# Weather_Station_Data_v3.net
KiCad netlist of a schematic drawn in EAGLE
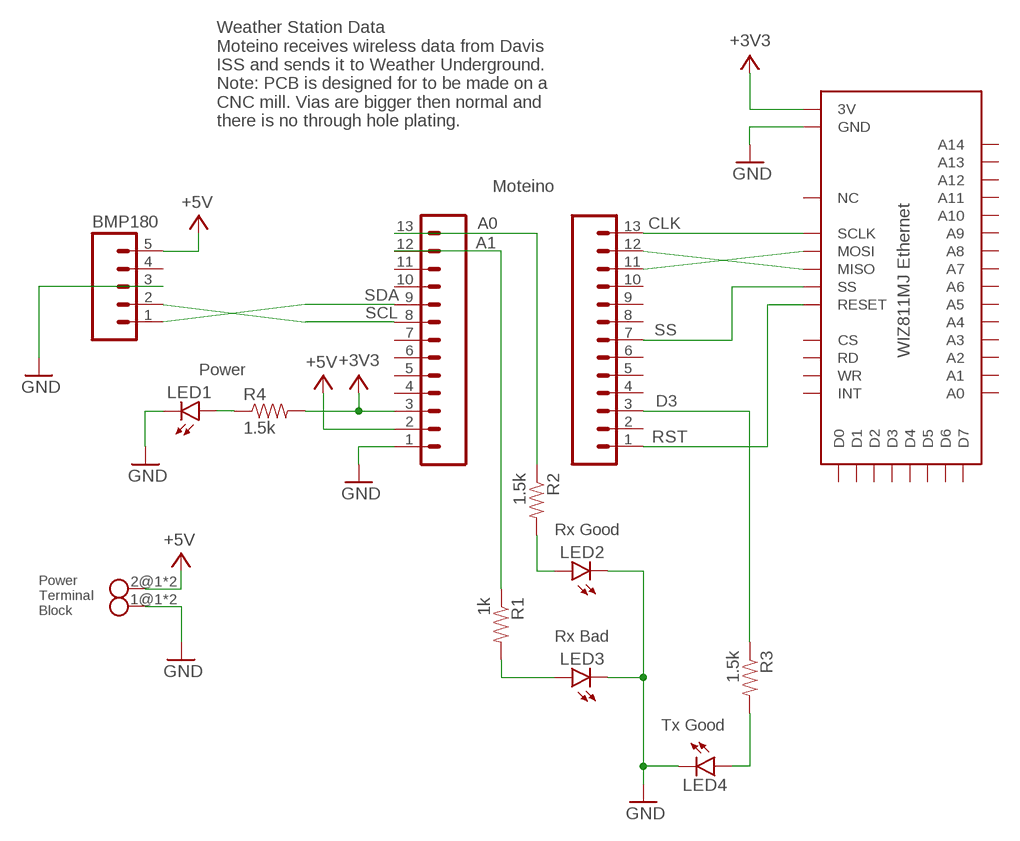
[diagram p0: schematic, sheet 1]

(export (version "E")
  (design (tool "Eeschema 10.0.6"))
  (components
    (comp (ref "BMP180")
      (value "M05PTH_LONGPADS")
      (footprint "eagle-import:1X05_LONGPADS")
      (libsource (lib "eagle-import") (part "M05PTH_LONGPADS"))
    )
    (comp (ref "JP1")
      (value "M13LONGPADS")
      (footprint "eagle-import:1X13-LONGPADS")
      (libsource (lib "eagle-import") (part "M13LONGPADS"))
    )
    (comp (ref "JP2")
      (value "M13LONGPADS")
      (footprint "eagle-import:1X13-LONGPADS")
      (libsource (lib "eagle-import") (part "M13LONGPADS"))
    )
    (comp (ref "LED1")
      (value "754-1440-1-ND")
      (footprint "eagle-import:LED-1206")
      (libsource (lib "eagle-import") (part "LED1206"))
    )
    (comp (ref "LED2")
      (value "754-1440-1-ND")
      (footprint "eagle-import:LED-1206")
      (libsource (lib "eagle-import") (part "LED1206"))
    )
    (comp (ref "LED3")
      (value "754-1143-1-ND")
      (footprint "eagle-import:LED-1206")
      (libsource (lib "eagle-import") (part "LED1206"))
    )
    (comp (ref "LED4")
      (value "754-1440-1-ND")
      (footprint "eagle-import:LED-1206")
      (libsource (lib "eagle-import") (part "LED1206"))
    )
    (comp (ref "POWER")
      (value "SPRING_TB_RT2")
      (footprint "eagle-import:SPRING_TB_RT2")
      (libsource (lib "eagle-import") (part "SPRING_TB_RT2"))
    )
    (comp (ref "R1")
      (value "1k")
      (footprint "eagle-import:AXIAL-0.3")
      (libsource (lib "eagle-import") (part "RESISTORAXIAL-0.3"))
    )
    (comp (ref "R2")
      (value "1.5k")
      (footprint "eagle-import:AXIAL-0.3")
      (libsource (lib "eagle-import") (part "RESISTORAXIAL-0.3"))
    )
    (comp (ref "R3")
      (value "1.5k")
      (footprint "eagle-import:AXIAL-0.3")
      (libsource (lib "eagle-import") (part "RESISTORAXIAL-0.3"))
    )
    (comp (ref "R4")
      (value "1.5k")
      (footprint "eagle-import:AXIAL-0.3")
      (libsource (lib "eagle-import") (part "RESISTORAXIAL-0.3"))
    )
    (comp (ref "U$1")
      (value "WIZ811MJ")
      (footprint "eagle-import:WIZ811MJ")
      (libsource (lib "eagle-import") (part "WIZ811MJ"))
    )
  )
  (nets
    (net (code "1") (name "+3V3") (class "Default")
      (node (ref "JP1") (pin "3") (pinfunction "3_3") (pintype "passive"))
      (node (ref "R4") (pin "P$2") (pinfunction "2_P$2") (pintype "passive"))
      (node (ref "U$1") (pin "3V@1") (pinfunction "3V_3V@1") (pintype "power_in"))
      (node (ref "U$1") (pin "3V@2") (pinfunction "3V_3V@2") (pintype "power_in"))
    )
    (net (code "2") (name "+5V") (class "Default")
      (node (ref "BMP180") (pin "5") (pinfunction "5_5") (pintype "passive"))
      (node (ref "JP1") (pin "2") (pinfunction "2_2") (pintype "passive"))
      (node (ref "POWER") (pin "2@1") (pinfunction "1_2@1") (pintype "passive"))
      (node (ref "POWER") (pin "2@2") (pinfunction "1_2@2") (pintype "passive"))
    )
    (net (code "3") (name "/A0") (class "Default")
      (node (ref "JP1") (pin "13") (pinfunction "13_13") (pintype "passive"))
      (node (ref "R2") (pin "P$1") (pinfunction "1_P$1") (pintype "passive"))
    )
    (net (code "4") (name "/A1") (class "Default")
      (node (ref "JP1") (pin "12") (pinfunction "12_12") (pintype "passive"))
      (node (ref "R1") (pin "P$1") (pinfunction "1_P$1") (pintype "passive"))
    )
    (net (code "5") (name "/CLK") (class "Default")
      (node (ref "JP2") (pin "13") (pinfunction "13_13") (pintype "passive"))
      (node (ref "U$1") (pin "SCLK") (pinfunction "SCLK_SCLK") (pintype "bidirectional"))
    )
    (net (code "6") (name "/D3") (class "Default")
      (node (ref "JP2") (pin "3") (pinfunction "3_3") (pintype "passive"))
      (node (ref "R3") (pin "P$1") (pinfunction "1_P$1") (pintype "passive"))
    )
    (net (code "7") (name "/RST") (class "Default")
      (node (ref "JP2") (pin "1") (pinfunction "1_1") (pintype "passive"))
      (node (ref "U$1") (pin "RESET") (pinfunction "RESET_RESET") (pintype "input"))
    )
    (net (code "8") (name "/SCL") (class "Default")
      (node (ref "BMP180") (pin "2") (pinfunction "2_2") (pintype "passive"))
      (node (ref "JP1") (pin "8") (pinfunction "8_8") (pintype "passive"))
    )
    (net (code "9") (name "/SDA") (class "Default")
      (node (ref "BMP180") (pin "1") (pinfunction "1_1") (pintype "passive"))
      (node (ref "JP1") (pin "9") (pinfunction "9_9") (pintype "passive"))
    )
    (net (code "10") (name "/SS") (class "Default")
      (node (ref "JP2") (pin "7") (pinfunction "7_7") (pintype "passive"))
      (node (ref "U$1") (pin "SCS") (pinfunction "SS_SCS") (pintype "bidirectional"))
    )
    (net (code "11") (name "GND") (class "Default")
      (node (ref "BMP180") (pin "3") (pinfunction "3_3") (pintype "passive"))
      (node (ref "JP1") (pin "1") (pinfunction "1_1") (pintype "passive"))
      (node (ref "LED1") (pin "C") (pinfunction "C_C") (pintype "passive"))
      (node (ref "LED2") (pin "C") (pinfunction "C_C") (pintype "passive"))
      (node (ref "LED3") (pin "C") (pinfunction "C_C") (pintype "passive"))
      (node (ref "LED4") (pin "C") (pinfunction "C_C") (pintype "passive"))
      (node (ref "POWER") (pin "1@1") (pinfunction "1_1@1") (pintype "passive"))
      (node (ref "POWER") (pin "1@2") (pinfunction "1_1@2") (pintype "passive"))
      (node (ref "U$1") (pin "GND@1") (pinfunction "GND_GND@1") (pintype "power_in"))
      (node (ref "U$1") (pin "GND@2") (pinfunction "GND_GND@2") (pintype "power_in"))
      (node (ref "U$1") (pin "GND@3") (pinfunction "GND_GND@3") (pintype "power_in"))
      (node (ref "U$1") (pin "GND@4") (pinfunction "GND_GND@4") (pintype "power_in"))
      (node (ref "U$1") (pin "GND@5") (pinfunction "GND_GND@5") (pintype "power_in"))
    )
    (net (code "12") (name "Net-(JP2-Pad11)") (class "Default")
      (node (ref "JP2") (pin "11") (pinfunction "11_11") (pintype "passive"))
      (node (ref "U$1") (pin "MOSI") (pinfunction "MOSI_MOSI") (pintype "bidirectional"))
    )
    (net (code "13") (name "Net-(JP2-Pad12)") (class "Default")
      (node (ref "JP2") (pin "12") (pinfunction "12_12") (pintype "passive"))
      (node (ref "U$1") (pin "MISO") (pinfunction "MISO_MISO") (pintype "bidirectional"))
    )
    (net (code "14") (name "Net-(R1-2)") (class "Default")
      (node (ref "LED3") (pin "A") (pinfunction "A_A") (pintype "passive"))
      (node (ref "R1") (pin "P$2") (pinfunction "2_P$2") (pintype "passive"))
    )
    (net (code "15") (name "Net-(R2-2)") (class "Default")
      (node (ref "LED2") (pin "A") (pinfunction "A_A") (pintype "passive"))
      (node (ref "R2") (pin "P$2") (pinfunction "2_P$2") (pintype "passive"))
    )
    (net (code "16") (name "Net-(R3-2)") (class "Default")
      (node (ref "LED4") (pin "A") (pinfunction "A_A") (pintype "passive"))
      (node (ref "R3") (pin "P$2") (pinfunction "2_P$2") (pintype "passive"))
    )
    (net (code "17") (name "Net-(R4-1)") (class "Default")
      (node (ref "LED1") (pin "A") (pinfunction "A_A") (pintype "passive"))
      (node (ref "R4") (pin "P$1") (pinfunction "1_P$1") (pintype "passive"))
    )
    (net (code "18") (name "unconnected-(BMP180-Pad4)") (class "Default")
      (node (ref "BMP180") (pin "4") (pinfunction "4_4") (pintype "passive"))
    )
    (net (code "19") (name "unconnected-(JP1-Pad4)") (class "Default")
      (node (ref "JP1") (pin "4") (pinfunction "4_4") (pintype "passive"))
    )
    (net (code "20") (name "unconnected-(JP1-Pad5)") (class "Default")
      (node (ref "JP1") (pin "5") (pinfunction "5_5") (pintype "passive"))
    )
    (net (code "21") (name "unconnected-(JP1-Pad6)") (class "Default")
      (node (ref "JP1") (pin "6") (pinfunction "6_6") (pintype "passive"))
    )
    (net (code "22") (name "unconnected-(JP1-Pad7)") (class "Default")
      (node (ref "JP1") (pin "7") (pinfunction "7_7") (pintype "passive"))
    )
    (net (code "23") (name "unconnected-(JP1-Pad10)") (class "Default")
      (node (ref "JP1") (pin "10") (pinfunction "10_10") (pintype "passive"))
    )
    (net (code "24") (name "unconnected-(JP1-Pad11)") (class "Default")
      (node (ref "JP1") (pin "11") (pinfunction "11_11") (pintype "passive"))
    )
    (net (code "25") (name "unconnected-(JP2-Pad2)") (class "Default")
      (node (ref "JP2") (pin "2") (pinfunction "2_2") (pintype "passive"))
    )
    (net (code "26") (name "unconnected-(JP2-Pad4)") (class "Default")
      (node (ref "JP2") (pin "4") (pinfunction "4_4") (pintype "passive"))
    )
    (net (code "27") (name "unconnected-(JP2-Pad5)") (class "Default")
      (node (ref "JP2") (pin "5") (pinfunction "5_5") (pintype "passive"))
    )
    (net (code "28") (name "unconnected-(JP2-Pad6)") (class "Default")
      (node (ref "JP2") (pin "6") (pinfunction "6_6") (pintype "passive"))
    )
    (net (code "29") (name "unconnected-(JP2-Pad8)") (class "Default")
      (node (ref "JP2") (pin "8") (pinfunction "8_8") (pintype "passive"))
    )
    (net (code "30") (name "unconnected-(JP2-Pad9)") (class "Default")
      (node (ref "JP2") (pin "9") (pinfunction "9_9") (pintype "passive"))
    )
    (net (code "31") (name "unconnected-(JP2-Pad10)") (class "Default")
      (node (ref "JP2") (pin "10") (pinfunction "10_10") (pintype "passive"))
    )
    (net (code "32") (name "unconnected-(U$1-PadA0)") (class "Default")
      (node (ref "U$1") (pin "A0") (pinfunction "A0_A0") (pintype "bidirectional"))
    )
    (net (code "33") (name "unconnected-(U$1-PadA1)") (class "Default")
      (node (ref "U$1") (pin "A1") (pinfunction "A1_A1") (pintype "bidirectional"))
    )
    (net (code "34") (name "unconnected-(U$1-PadA2)") (class "Default")
      (node (ref "U$1") (pin "A2") (pinfunction "A2_A2") (pintype "bidirectional"))
    )
    (net (code "35") (name "unconnected-(U$1-PadA3)") (class "Default")
      (node (ref "U$1") (pin "A3") (pinfunction "A3_A3") (pintype "bidirectional"))
    )
    (net (code "36") (name "unconnected-(U$1-PadA4)") (class "Default")
      (node (ref "U$1") (pin "A4") (pinfunction "A4_A4") (pintype "bidirectional"))
    )
    (net (code "37") (name "unconnected-(U$1-PadA5)") (class "Default")
      (node (ref "U$1") (pin "A5") (pinfunction "A5_A5") (pintype "bidirectional"))
    )
    (net (code "38") (name "unconnected-(U$1-PadA6)") (class "Default")
      (node (ref "U$1") (pin "A6") (pinfunction "A6_A6") (pintype "bidirectional"))
    )
    (net (code "39") (name "unconnected-(U$1-PadA7)") (class "Default")
      (node (ref "U$1") (pin "A7") (pinfunction "A7_A7") (pintype "bidirectional"))
    )
    (net (code "40") (name "unconnected-(U$1-PadA8)") (class "Default")
      (node (ref "U$1") (pin "A8") (pinfunction "A8_A8") (pintype "bidirectional"))
    )
    (net (code "41") (name "unconnected-(U$1-PadA9)") (class "Default")
      (node (ref "U$1") (pin "A9") (pinfunction "A9_A9") (pintype "bidirectional"))
    )
    (net (code "42") (name "unconnected-(U$1-PadA10)") (class "Default")
      (node (ref "U$1") (pin "A10") (pinfunction "A10_A10") (pintype "bidirectional"))
    )
    (net (code "43") (name "unconnected-(U$1-PadA11)") (class "Default")
      (node (ref "U$1") (pin "A11") (pinfunction "A11_A11") (pintype "bidirectional"))
    )
    (net (code "44") (name "unconnected-(U$1-PadA12)") (class "Default")
      (node (ref "U$1") (pin "A12") (pinfunction "A12_A12") (pintype "bidirectional"))
    )
    (net (code "45") (name "unconnected-(U$1-PadA13)") (class "Default")
      (node (ref "U$1") (pin "A13") (pinfunction "A13_A13") (pintype "bidirectional"))
    )
    (net (code "46") (name "unconnected-(U$1-PadA14)") (class "Default")
      (node (ref "U$1") (pin "A14") (pinfunction "A14_A14") (pintype "bidirectional"))
    )
    (net (code "47") (name "unconnected-(U$1-PadCS)") (class "Default")
      (node (ref "U$1") (pin "CS") (pinfunction "CS_CS") (pintype "bidirectional"))
    )
    (net (code "48") (name "unconnected-(U$1-PadD0)") (class "Default")
      (node (ref "U$1") (pin "D0") (pinfunction "D0_D0") (pintype "bidirectional"))
    )
    (net (code "49") (name "unconnected-(U$1-PadD1)") (class "Default")
      (node (ref "U$1") (pin "D1") (pinfunction "D1_D1") (pintype "bidirectional"))
    )
    (net (code "50") (name "unconnected-(U$1-PadD2)") (class "Default")
      (node (ref "U$1") (pin "D2") (pinfunction "D2_D2") (pintype "bidirectional"))
    )
    (net (code "51") (name "unconnected-(U$1-PadD3)") (class "Default")
      (node (ref "U$1") (pin "D3") (pinfunction "D3_D3") (pintype "bidirectional"))
    )
    (net (code "52") (name "unconnected-(U$1-PadD4)") (class "Default")
      (node (ref "U$1") (pin "D4") (pinfunction "D4_D4") (pintype "bidirectional"))
    )
    (net (code "53") (name "unconnected-(U$1-PadD5)") (class "Default")
      (node (ref "U$1") (pin "D5") (pinfunction "D5_D5") (pintype "bidirectional"))
    )
    (net (code "54") (name "unconnected-(U$1-PadD6)") (class "Default")
      (node (ref "U$1") (pin "D6") (pinfunction "D6_D6") (pintype "bidirectional"))
    )
    (net (code "55") (name "unconnected-(U$1-PadD7)") (class "Default")
      (node (ref "U$1") (pin "D7") (pinfunction "D7_D7") (pintype "bidirectional"))
    )
    (net (code "56") (name "unconnected-(U$1-PadINT)") (class "Default")
      (node (ref "U$1") (pin "INT") (pinfunction "INT_INT") (pintype "bidirectional"))
    )
    (net (code "57") (name "unconnected-(U$1-PadNC)") (class "Default")
      (node (ref "U$1") (pin "NC") (pinfunction "NC_NC") (pintype "no_connect"))
    )
    (net (code "58") (name "unconnected-(U$1-PadRD)") (class "Default")
      (node (ref "U$1") (pin "RD") (pinfunction "RD_RD") (pintype "bidirectional"))
    )
    (net (code "59") (name "unconnected-(U$1-PadWR)") (class "Default")
      (node (ref "U$1") (pin "WR") (pinfunction "WR_WR") (pintype "bidirectional"))
    )
  )
)
